# pic32.net
KiCad netlist of a schematic drawn in EAGLE
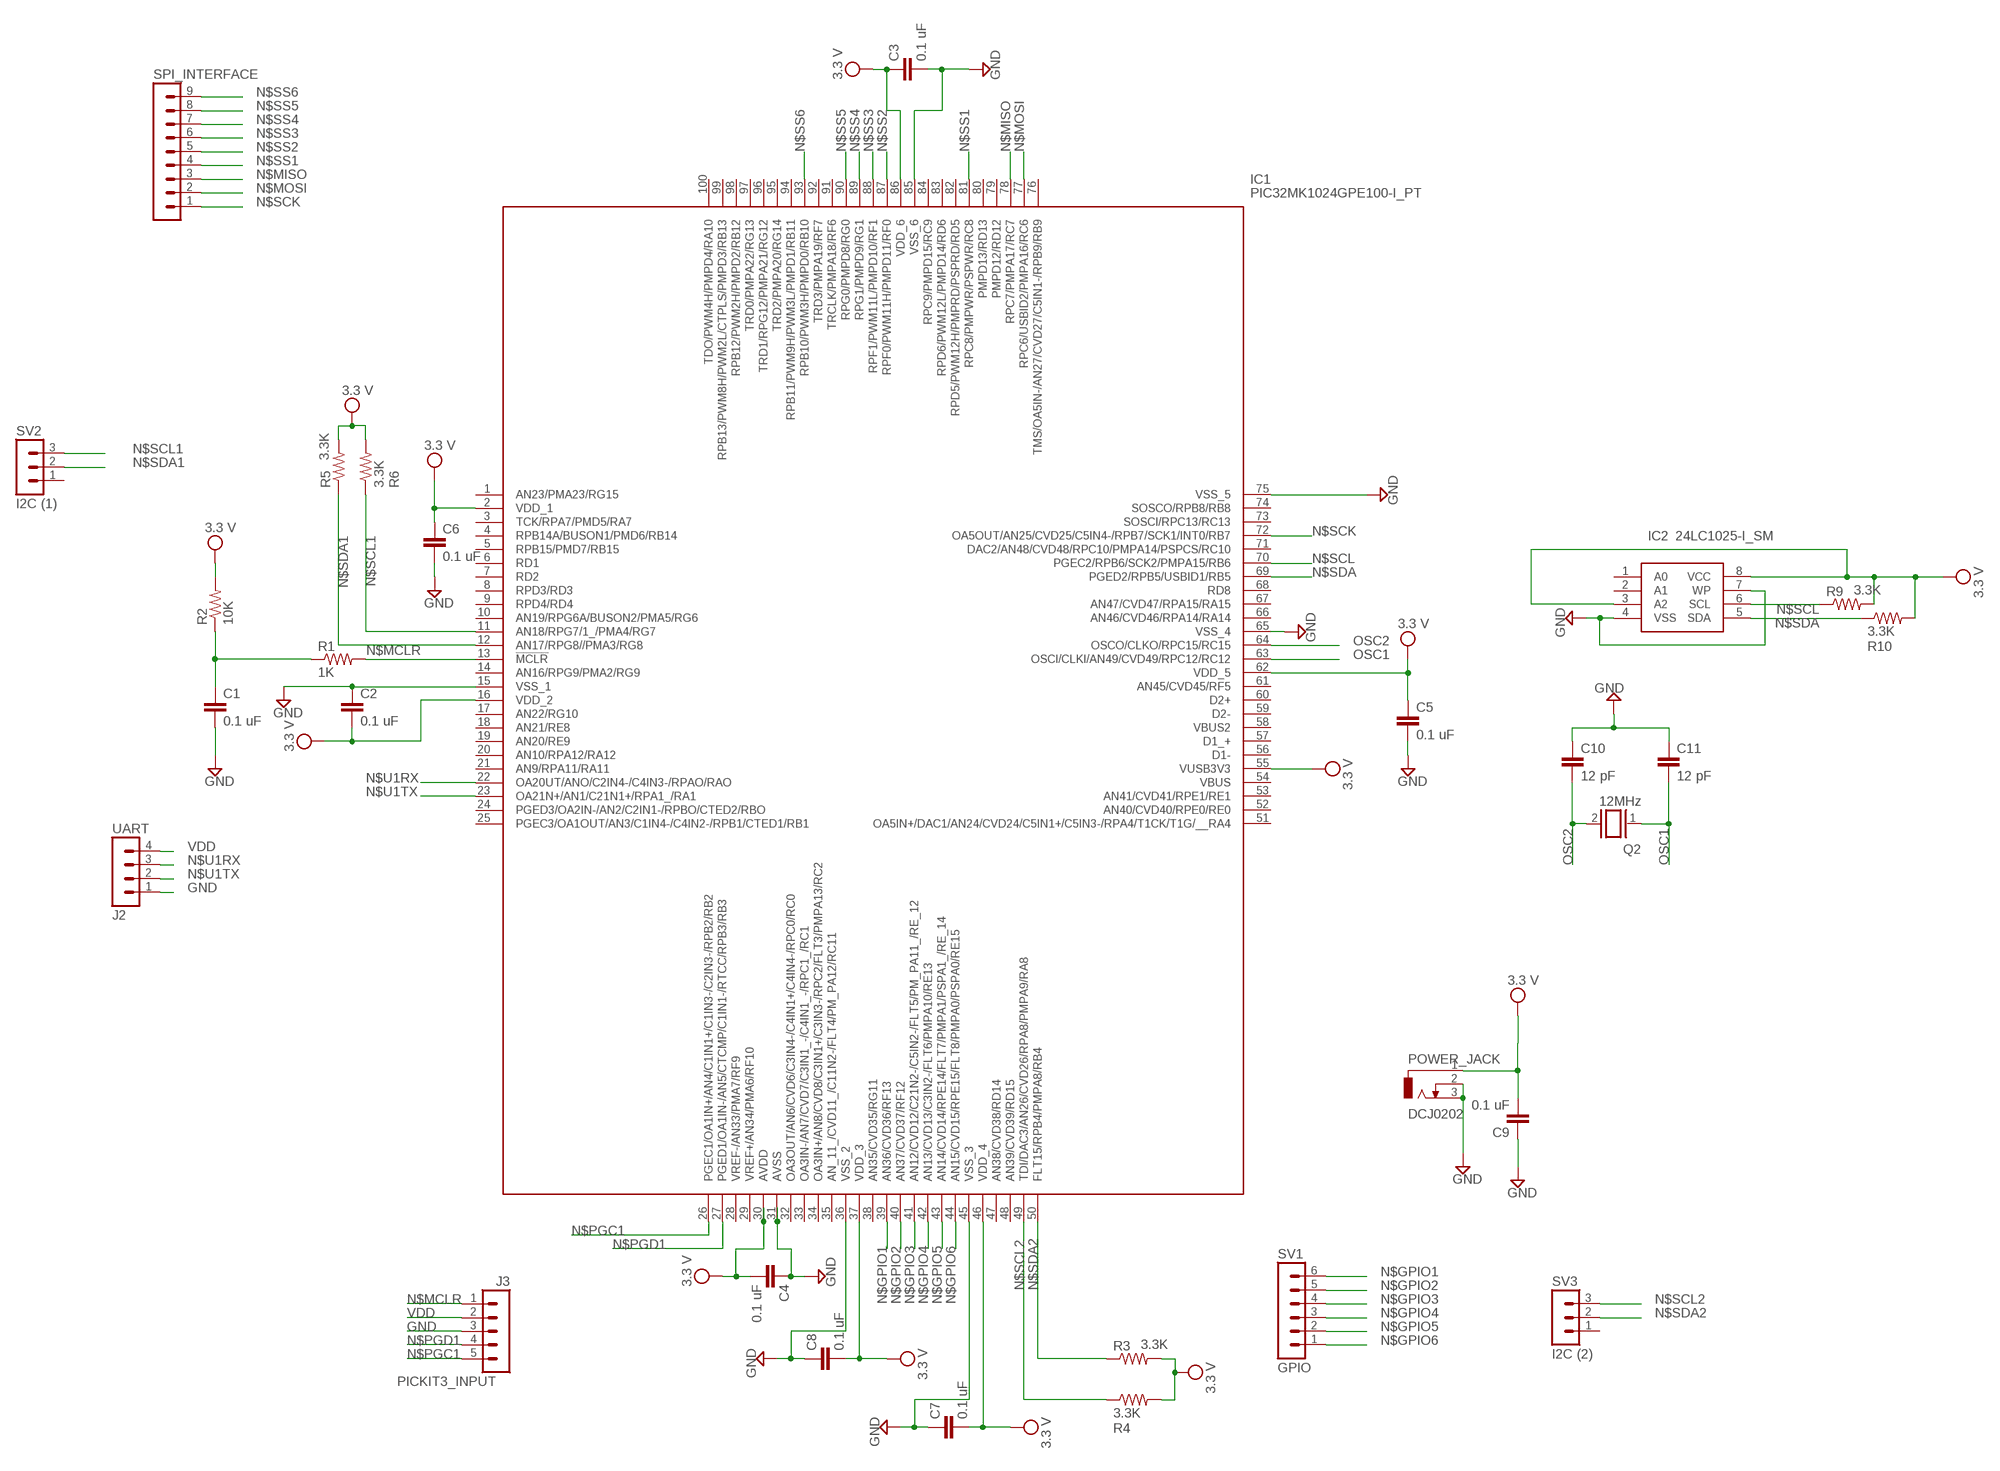
[diagram p0: schematic, sheet 1]

(export (version "E")
  (design (tool "Eeschema 10.0.6"))
  (components
    (comp (ref "C1")
      (value "0.1 uF")
      (footprint "eagle-import:C025-025X050")
      (libsource (lib "eagle-import") (part "C-EU025-025X050"))
    )
    (comp (ref "C2")
      (value "0.1 uF")
      (footprint "eagle-import:C025-025X050")
      (libsource (lib "eagle-import") (part "C-EU025-025X050"))
    )
    (comp (ref "C3")
      (value "0.1 uF")
      (footprint "eagle-import:C025-025X050")
      (libsource (lib "eagle-import") (part "C-EU025-025X050"))
    )
    (comp (ref "C4")
      (value "0.1 uF")
      (footprint "eagle-import:C025-025X050")
      (libsource (lib "eagle-import") (part "C-EU025-025X050"))
    )
    (comp (ref "C5")
      (value "0.1 uF")
      (footprint "eagle-import:C025-025X050")
      (libsource (lib "eagle-import") (part "C-EU025-025X050"))
    )
    (comp (ref "C6")
      (value "0.1 uF")
      (footprint "eagle-import:C025-025X050")
      (libsource (lib "eagle-import") (part "C-EU025-025X050"))
    )
    (comp (ref "C7")
      (value "0.1 uF")
      (footprint "eagle-import:C025-025X050")
      (libsource (lib "eagle-import") (part "C-EU025-025X050"))
    )
    (comp (ref "C8")
      (value "0.1 uF")
      (footprint "eagle-import:C025-025X050")
      (libsource (lib "eagle-import") (part "C-EU025-025X050"))
    )
    (comp (ref "C9")
      (value "0.1 uF")
      (footprint "eagle-import:C025-025X050")
      (libsource (lib "eagle-import") (part "C-EU025-025X050"))
    )
    (comp (ref "C10")
      (value "12 pF")
      (footprint "eagle-import:C025-025X050")
      (libsource (lib "eagle-import") (part "C-EU025-025X050"))
    )
    (comp (ref "C11")
      (value "12 pF")
      (footprint "eagle-import:C025-025X050")
      (libsource (lib "eagle-import") (part "C-EU025-025X050"))
    )
    (comp (ref "IC1")
      (value "PIC32MK1024GPE100-I_PT")
      (footprint "eagle-import:QFP40P1400X1400X120-100N")
      (fields
        (field (name "MANUFACTURER_PART_NUMBER") "PIC32MK1024GPE100-I/PT")
        (field (name "MOUSER_PART_NUMBER") "579-2MK1024GPE100IPT")
      )
      (libsource (lib "eagle-import") (part "PIC32MK1024GPE100-I_PT"))
    )
    (comp (ref "IC2")
      (value "24LC1025-I_SM")
      (footprint "eagle-import:SOIC127P794X203-8N")
      (fields
        (field (name "MANUFACTURER_PART_NUMBER") "24LC1025-I/SM")
        (field (name "MOUSER_PART_NUMBER") "579-24LC1025-I/SM")
      )
      (libsource (lib "eagle-import") (part "24LC1025-I_SM"))
    )
    (comp (ref "PICKIT3_INPUT")
      (value "J3")
      (footprint "eagle-import:MA05-1")
      (libsource (lib "eagle-import") (part "MA05-1"))
    )
    (comp (ref "POWER_JACK")
      (value "DCJ0202")
      (footprint "eagle-import:DCJ0202")
      (libsource (lib "eagle-import") (part "DCJ0202"))
    )
    (comp (ref "Q2")
      (value "12MHz")
      (footprint "eagle-import:QS")
      (libsource (lib "eagle-import") (part "XTAL/S"))
    )
    (comp (ref "R1")
      (value "1K")
      (footprint "eagle-import:0207_7")
      (libsource (lib "eagle-import") (part "R-US_0207/7"))
    )
    (comp (ref "R2")
      (value "10K")
      (footprint "eagle-import:0207_7")
      (libsource (lib "eagle-import") (part "R-US_0207/7"))
    )
    (comp (ref "R3")
      (value "3.3K")
      (footprint "eagle-import:0207_7")
      (libsource (lib "eagle-import") (part "R-US_0207/7"))
    )
    (comp (ref "R4")
      (value "3.3K")
      (footprint "eagle-import:0207_7")
      (libsource (lib "eagle-import") (part "R-US_0207/7"))
    )
    (comp (ref "R5")
      (value "3.3K")
      (footprint "eagle-import:0207_7")
      (libsource (lib "eagle-import") (part "R-US_0207/7"))
    )
    (comp (ref "R6")
      (value "3.3K")
      (footprint "eagle-import:0207_7")
      (libsource (lib "eagle-import") (part "R-US_0207/7"))
    )
    (comp (ref "R9")
      (value "3.3K")
      (footprint "eagle-import:0207_7")
      (libsource (lib "eagle-import") (part "R-US_0207/7"))
    )
    (comp (ref "R10")
      (value "3.3K")
      (footprint "eagle-import:0207_7")
      (libsource (lib "eagle-import") (part "R-US_0207/7"))
    )
    (comp (ref "SPI_INTERFACE")
      (value "J1")
      (footprint "eagle-import:MA09-1")
      (libsource (lib "eagle-import") (part "MA09-1"))
    )
    (comp (ref "SV1")
      (value "GPIO")
      (footprint "eagle-import:MA06-1")
      (libsource (lib "eagle-import") (part "MA06-1"))
    )
    (comp (ref "SV2")
      (value "I2C (1)")
      (footprint "eagle-import:MA03-1")
      (libsource (lib "eagle-import") (part "MA03-1"))
    )
    (comp (ref "SV3")
      (value "I2C (2)")
      (footprint "eagle-import:MA03-1")
      (libsource (lib "eagle-import") (part "MA03-1"))
    )
    (comp (ref "UART")
      (value "J2")
      (footprint "eagle-import:MA04-1")
      (libsource (lib "eagle-import") (part "MA04-1"))
    )
  )
  (nets
    (net (code "1") (name "/N$GPIO1") (class "Default")
      (node (ref "IC1") (pin "39") (pinfunction "AN36/CVD36/RF13_39") (pintype "bidirectional"))
      (node (ref "SV1") (pin "6") (pinfunction "6_6") (pintype "passive"))
    )
    (net (code "2") (name "/N$GPIO2") (class "Default")
      (node (ref "IC1") (pin "40") (pinfunction "AN37/CVD37/RF12_40") (pintype "bidirectional"))
      (node (ref "SV1") (pin "5") (pinfunction "5_5") (pintype "passive"))
    )
    (net (code "3") (name "/N$GPIO3") (class "Default")
      (node (ref "IC1") (pin "41") (pinfunction "AN12/CVD12/C21N2-/C5IN2-/FLT5/PM_PA11_/RE_12_41") (pintype "bidirectional"))
      (node (ref "SV1") (pin "4") (pinfunction "4_4") (pintype "passive"))
    )
    (net (code "4") (name "/N$GPIO4") (class "Default")
      (node (ref "IC1") (pin "42") (pinfunction "AN13/CVD13/C3IN2-/FLT6/PMPA10/RE13_42") (pintype "bidirectional"))
      (node (ref "SV1") (pin "3") (pinfunction "3_3") (pintype "passive"))
    )
    (net (code "5") (name "/N$GPIO5") (class "Default")
      (node (ref "IC1") (pin "43") (pinfunction "AN14/CVD14/RPE14/FLT7/PMPA1/PSPA1_/RE_14_43") (pintype "bidirectional"))
      (node (ref "SV1") (pin "2") (pinfunction "2_2") (pintype "passive"))
    )
    (net (code "6") (name "/N$GPIO6") (class "Default")
      (node (ref "IC1") (pin "44") (pinfunction "AN15/CVD15/RPE15/FLT8/PMPA0/PSPA0/RE15_44") (pintype "bidirectional"))
      (node (ref "SV1") (pin "1") (pinfunction "1_1") (pintype "passive"))
    )
    (net (code "7") (name "/N$MCLR") (class "Default")
      (node (ref "IC1") (pin "13") (pinfunction "~{MCLR}_13") (pintype "bidirectional"))
      (node (ref "PICKIT3_INPUT") (pin "1") (pinfunction "1_1") (pintype "passive"))
      (node (ref "R1") (pin "2") (pinfunction "2_2") (pintype "passive"))
    )
    (net (code "8") (name "/N$MISO") (class "Default")
      (node (ref "IC1") (pin "78") (pinfunction "RPC7/PMPA17/RC7_78") (pintype "bidirectional"))
      (node (ref "SPI_INTERFACE") (pin "3") (pinfunction "3_3") (pintype "passive"))
    )
    (net (code "9") (name "/N$MOSI") (class "Default")
      (node (ref "IC1") (pin "77") (pinfunction "RPC6/USBID2/PMPA16/RC6_77") (pintype "bidirectional"))
      (node (ref "SPI_INTERFACE") (pin "2") (pinfunction "2_2") (pintype "passive"))
    )
    (net (code "10") (name "/N$PGC1") (class "Default")
      (node (ref "IC1") (pin "26") (pinfunction "PGEC1/OA1IN+/AN4/C1IN1+/C1IN3-/C2IN3-/RPB2/RB2_26") (pintype "bidirectional"))
      (node (ref "PICKIT3_INPUT") (pin "5") (pinfunction "5_5") (pintype "passive"))
    )
    (net (code "11") (name "/N$PGD1") (class "Default")
      (node (ref "IC1") (pin "27") (pinfunction "PGED1/OA1IN-/AN5/CTCMP/C1IN1-/RTCC/RPB3/RB3_27") (pintype "bidirectional"))
      (node (ref "PICKIT3_INPUT") (pin "4") (pinfunction "4_4") (pintype "passive"))
    )
    (net (code "12") (name "/N$SCK") (class "Default")
      (node (ref "IC1") (pin "72") (pinfunction "OA5OUT/AN25/CVD25/C5IN4-/RPB7/SCK1/INT0/RB7_72") (pintype "bidirectional"))
      (node (ref "SPI_INTERFACE") (pin "1") (pinfunction "1_1") (pintype "passive"))
    )
    (net (code "13") (name "/N$SCL") (class "Default")
      (node (ref "IC1") (pin "70") (pinfunction "PGEC2/RPB6/SCK2/PMPA15/RB6_70") (pintype "bidirectional"))
      (node (ref "IC2") (pin "6") (pinfunction "SCL_6") (pintype "bidirectional"))
      (node (ref "R9") (pin "1") (pinfunction "1_1") (pintype "passive"))
    )
    (net (code "14") (name "/N$SCL1") (class "Default")
      (node (ref "IC1") (pin "11") (pinfunction "AN18/RPG7/1_/PMA4/RG7_11") (pintype "bidirectional"))
      (node (ref "R6") (pin "1") (pinfunction "1_1") (pintype "passive"))
      (node (ref "SV2") (pin "3") (pinfunction "3_3") (pintype "passive"))
    )
    (net (code "15") (name "/N$SCL2") (class "Default")
      (node (ref "IC1") (pin "49") (pinfunction "TDI/DAC3/AN26/CVD26/RPA8/PMPA9/RA8_49") (pintype "bidirectional"))
      (node (ref "R4") (pin "1") (pinfunction "1_1") (pintype "passive"))
      (node (ref "SV3") (pin "3") (pinfunction "3_3") (pintype "passive"))
    )
    (net (code "16") (name "/N$SDA") (class "Default")
      (node (ref "IC1") (pin "69") (pinfunction "PGED2/RPB5/USBID1/RB5_69") (pintype "bidirectional"))
      (node (ref "IC2") (pin "5") (pinfunction "SDA_5") (pintype "bidirectional"))
      (node (ref "R10") (pin "1") (pinfunction "1_1") (pintype "passive"))
    )
    (net (code "17") (name "/N$SDA1") (class "Default")
      (node (ref "IC1") (pin "12") (pinfunction "AN17/RPG8//PMA3/RG8_12") (pintype "bidirectional"))
      (node (ref "R5") (pin "1") (pinfunction "1_1") (pintype "passive"))
      (node (ref "SV2") (pin "2") (pinfunction "2_2") (pintype "passive"))
    )
    (net (code "18") (name "/N$SDA2") (class "Default")
      (node (ref "IC1") (pin "50") (pinfunction "FLT15/RPB4/PMPA8/RB4_50") (pintype "bidirectional"))
      (node (ref "R3") (pin "1") (pinfunction "1_1") (pintype "passive"))
      (node (ref "SV3") (pin "2") (pinfunction "2_2") (pintype "passive"))
    )
    (net (code "19") (name "/N$SS1") (class "Default")
      (node (ref "IC1") (pin "81") (pinfunction "RPC8/PMPWR/PSPWR/RC8_81") (pintype "bidirectional"))
      (node (ref "SPI_INTERFACE") (pin "4") (pinfunction "4_4") (pintype "passive"))
    )
    (net (code "20") (name "/N$SS2") (class "Default")
      (node (ref "IC1") (pin "87") (pinfunction "RPF0/PWM11H/PMPD11/RF0_87") (pintype "bidirectional"))
      (node (ref "SPI_INTERFACE") (pin "5") (pinfunction "5_5") (pintype "passive"))
    )
    (net (code "21") (name "/N$SS3") (class "Default")
      (node (ref "IC1") (pin "88") (pinfunction "RPF1/PWM11L/PMPD10/RF1_88") (pintype "bidirectional"))
      (node (ref "SPI_INTERFACE") (pin "6") (pinfunction "6_6") (pintype "passive"))
    )
    (net (code "22") (name "/N$SS4") (class "Default")
      (node (ref "IC1") (pin "89") (pinfunction "RPG1/PMPD9/RG1_89") (pintype "bidirectional"))
      (node (ref "SPI_INTERFACE") (pin "7") (pinfunction "7_7") (pintype "passive"))
    )
    (net (code "23") (name "/N$SS5") (class "Default")
      (node (ref "IC1") (pin "90") (pinfunction "RPG0/PMPD8/RG0_90") (pintype "bidirectional"))
      (node (ref "SPI_INTERFACE") (pin "8") (pinfunction "8_8") (pintype "passive"))
    )
    (net (code "24") (name "/N$SS6") (class "Default")
      (node (ref "IC1") (pin "93") (pinfunction "RPB10/PWM3H/PMPD0/RB10_93") (pintype "bidirectional"))
      (node (ref "SPI_INTERFACE") (pin "9") (pinfunction "9_9") (pintype "passive"))
    )
    (net (code "25") (name "/N$U1RX") (class "Default")
      (node (ref "IC1") (pin "22") (pinfunction "OA20UT/ANO/C2IN4-/C4IN3-/RPAO/RAO_22") (pintype "bidirectional"))
      (node (ref "UART") (pin "3") (pinfunction "3_3") (pintype "passive"))
    )
    (net (code "26") (name "/N$U1TX") (class "Default")
      (node (ref "IC1") (pin "23") (pinfunction "OA21N+/AN1/C21N1+/RPA1_/RA1_23") (pintype "bidirectional"))
      (node (ref "UART") (pin "2") (pinfunction "2_2") (pintype "passive"))
    )
    (net (code "27") (name "/OSC1") (class "Default")
      (node (ref "C11") (pin "2") (pinfunction "2_2") (pintype "passive"))
      (node (ref "IC1") (pin "63") (pinfunction "OSCI/CLKI/AN49/CVD49/RPC12/RC12_63") (pintype "bidirectional"))
      (node (ref "Q2") (pin "1") (pinfunction "1_1") (pintype "passive"))
    )
    (net (code "28") (name "/OSC2") (class "Default")
      (node (ref "C10") (pin "2") (pinfunction "2_2") (pintype "passive"))
      (node (ref "IC1") (pin "64") (pinfunction "OSCO/CLKO/RPC15/RC15_64") (pintype "bidirectional"))
      (node (ref "Q2") (pin "2") (pinfunction "2_2") (pintype "passive"))
    )
    (net (code "29") (name "3.3 V") (class "Default")
      (node (ref "C2") (pin "2") (pinfunction "2_2") (pintype "passive"))
      (node (ref "C3") (pin "1") (pinfunction "1_1") (pintype "passive"))
      (node (ref "C4") (pin "2") (pinfunction "2_2") (pintype "passive"))
      (node (ref "C5") (pin "1") (pinfunction "1_1") (pintype "passive"))
      (node (ref "C6") (pin "1") (pinfunction "1_1") (pintype "passive"))
      (node (ref "C7") (pin "2") (pinfunction "2_2") (pintype "passive"))
      (node (ref "C8") (pin "2") (pinfunction "2_2") (pintype "passive"))
      (node (ref "C9") (pin "2") (pinfunction "2_2") (pintype "passive"))
      (node (ref "IC1") (pin "16") (pinfunction "VDD_2_16") (pintype "bidirectional"))
      (node (ref "IC1") (pin "2") (pinfunction "VDD_1_2") (pintype "bidirectional"))
      (node (ref "IC1") (pin "30") (pinfunction "AVDD_30") (pintype "bidirectional"))
      (node (ref "IC1") (pin "37") (pinfunction "VDD_3_37") (pintype "bidirectional"))
      (node (ref "IC1") (pin "46") (pinfunction "VDD_4_46") (pintype "bidirectional"))
      (node (ref "IC1") (pin "55") (pinfunction "VUSB3V3_55") (pintype "bidirectional"))
      (node (ref "IC1") (pin "62") (pinfunction "VDD_5_62") (pintype "bidirectional"))
      (node (ref "IC1") (pin "86") (pinfunction "VDD_6_86") (pintype "bidirectional"))
      (node (ref "IC2") (pin "3") (pinfunction "A2_3") (pintype "bidirectional"))
      (node (ref "IC2") (pin "8") (pinfunction "VCC_8") (pintype "power_in"))
      (node (ref "PICKIT3_INPUT") (pin "2") (pinfunction "2_2") (pintype "passive"))
      (node (ref "POWER_JACK") (pin "1") (pinfunction "1_1") (pintype "passive"))
      (node (ref "R10") (pin "2") (pinfunction "2_2") (pintype "passive"))
      (node (ref "R2") (pin "2") (pinfunction "2_2") (pintype "passive"))
      (node (ref "R3") (pin "2") (pinfunction "2_2") (pintype "passive"))
      (node (ref "R4") (pin "2") (pinfunction "2_2") (pintype "passive"))
      (node (ref "R5") (pin "2") (pinfunction "2_2") (pintype "passive"))
      (node (ref "R6") (pin "2") (pinfunction "2_2") (pintype "passive"))
      (node (ref "R9") (pin "2") (pinfunction "2_2") (pintype "passive"))
      (node (ref "UART") (pin "4") (pinfunction "4_4") (pintype "passive"))
    )
    (net (code "30") (name "GND") (class "Default")
      (node (ref "C1") (pin "2") (pinfunction "2_2") (pintype "passive"))
      (node (ref "C10") (pin "1") (pinfunction "1_1") (pintype "passive"))
      (node (ref "C11") (pin "1") (pinfunction "1_1") (pintype "passive"))
      (node (ref "C2") (pin "1") (pinfunction "1_1") (pintype "passive"))
      (node (ref "C3") (pin "2") (pinfunction "2_2") (pintype "passive"))
      (node (ref "C4") (pin "1") (pinfunction "1_1") (pintype "passive"))
      (node (ref "C5") (pin "2") (pinfunction "2_2") (pintype "passive"))
      (node (ref "C6") (pin "2") (pinfunction "2_2") (pintype "passive"))
      (node (ref "C7") (pin "1") (pinfunction "1_1") (pintype "passive"))
      (node (ref "C8") (pin "1") (pinfunction "1_1") (pintype "passive"))
      (node (ref "C9") (pin "1") (pinfunction "1_1") (pintype "passive"))
      (node (ref "IC1") (pin "15") (pinfunction "VSS_1_15") (pintype "bidirectional"))
      (node (ref "IC1") (pin "31") (pinfunction "AVSS_31") (pintype "bidirectional"))
      (node (ref "IC1") (pin "36") (pinfunction "VSS_2_36") (pintype "bidirectional"))
      (node (ref "IC1") (pin "45") (pinfunction "VSS_3_45") (pintype "bidirectional"))
      (node (ref "IC1") (pin "65") (pinfunction "VSS_4_65") (pintype "bidirectional"))
      (node (ref "IC1") (pin "75") (pinfunction "VSS_5_75") (pintype "bidirectional"))
      (node (ref "IC1") (pin "85") (pinfunction "VSS_6_85") (pintype "bidirectional"))
      (node (ref "IC2") (pin "4") (pinfunction "VSS_4") (pintype "power_in"))
      (node (ref "IC2") (pin "7") (pinfunction "WP_7") (pintype "bidirectional"))
      (node (ref "PICKIT3_INPUT") (pin "3") (pinfunction "3_3") (pintype "passive"))
      (node (ref "POWER_JACK") (pin "2") (pinfunction "2_2") (pintype "passive"))
      (node (ref "POWER_JACK") (pin "3") (pinfunction "3_3") (pintype "passive"))
      (node (ref "UART") (pin "1") (pinfunction "1_1") (pintype "passive"))
    )
    (net (code "31") (name "Net-(C1-Pad1)") (class "Default")
      (node (ref "C1") (pin "1") (pinfunction "1_1") (pintype "passive"))
      (node (ref "R1") (pin "1") (pinfunction "1_1") (pintype "passive"))
      (node (ref "R2") (pin "1") (pinfunction "1_1") (pintype "passive"))
    )
    (net (code "32") (name "unconnected-(IC1-AN9{slash}RPA11{slash}RA11-Pad21)") (class "Default")
      (node (ref "IC1") (pin "21") (pinfunction "AN9/RPA11/RA11_21") (pintype "bidirectional"))
    )
    (net (code "33") (name "unconnected-(IC1-AN10{slash}RPA12{slash}RA12-Pad20)") (class "Default")
      (node (ref "IC1") (pin "20") (pinfunction "AN10/RPA12/RA12_20") (pintype "bidirectional"))
    )
    (net (code "34") (name "unconnected-(IC1-AN16{slash}RPG9{slash}PMA2{slash}RG9-Pad14)") (class "Default")
      (node (ref "IC1") (pin "14") (pinfunction "AN16/RPG9/PMA2/RG9_14") (pintype "bidirectional"))
    )
    (net (code "35") (name "unconnected-(IC1-AN19{slash}RPG6A{slash}BUSON2{slash}PMA5{slash}RG6-Pad10)") (class "Default")
      (node (ref "IC1") (pin "10") (pinfunction "AN19/RPG6A/BUSON2/PMA5/RG6_10") (pintype "bidirectional"))
    )
    (net (code "36") (name "unconnected-(IC1-AN20{slash}RE9-Pad19)") (class "Default")
      (node (ref "IC1") (pin "19") (pinfunction "AN20/RE9_19") (pintype "bidirectional"))
    )
    (net (code "37") (name "unconnected-(IC1-AN21{slash}RE8-Pad18)") (class "Default")
      (node (ref "IC1") (pin "18") (pinfunction "AN21/RE8_18") (pintype "bidirectional"))
    )
    (net (code "38") (name "unconnected-(IC1-AN22{slash}RG10-Pad17)") (class "Default")
      (node (ref "IC1") (pin "17") (pinfunction "AN22/RG10_17") (pintype "bidirectional"))
    )
    (net (code "39") (name "unconnected-(IC1-AN23{slash}PMA23{slash}RG15-Pad1)") (class "Default")
      (node (ref "IC1") (pin "1") (pinfunction "AN23/PMA23/RG15_1") (pintype "bidirectional"))
    )
    (net (code "40") (name "unconnected-(IC1-AN35{slash}CVD35{slash}RG11-Pad38)") (class "Default")
      (node (ref "IC1") (pin "38") (pinfunction "AN35/CVD35/RG11_38") (pintype "bidirectional"))
    )
    (net (code "41") (name "unconnected-(IC1-AN38{slash}CVD38{slash}RD14-Pad47)") (class "Default")
      (node (ref "IC1") (pin "47") (pinfunction "AN38/CVD38/RD14_47") (pintype "bidirectional"))
    )
    (net (code "42") (name "unconnected-(IC1-AN39{slash}CVD39{slash}RD15-Pad48)") (class "Default")
      (node (ref "IC1") (pin "48") (pinfunction "AN39/CVD39/RD15_48") (pintype "bidirectional"))
    )
    (net (code "43") (name "unconnected-(IC1-AN40{slash}CVD40{slash}RPE0{slash}RE0-Pad52)") (class "Default")
      (node (ref "IC1") (pin "52") (pinfunction "AN40/CVD40/RPE0/RE0_52") (pintype "bidirectional"))
    )
    (net (code "44") (name "unconnected-(IC1-AN41{slash}CVD41{slash}RPE1{slash}RE1-Pad53)") (class "Default")
      (node (ref "IC1") (pin "53") (pinfunction "AN41/CVD41/RPE1/RE1_53") (pintype "bidirectional"))
    )
    (net (code "45") (name "unconnected-(IC1-AN45{slash}CVD45{slash}RF5-Pad61)") (class "Default")
      (node (ref "IC1") (pin "61") (pinfunction "AN45/CVD45/RF5_61") (pintype "bidirectional"))
    )
    (net (code "46") (name "unconnected-(IC1-AN46{slash}CVD46{slash}RPA14{slash}RA14-Pad66)") (class "Default")
      (node (ref "IC1") (pin "66") (pinfunction "AN46/CVD46/RPA14/RA14_66") (pintype "bidirectional"))
    )
    (net (code "47") (name "unconnected-(IC1-AN47{slash}CVD47{slash}RPA15{slash}RA15-Pad67)") (class "Default")
      (node (ref "IC1") (pin "67") (pinfunction "AN47/CVD47/RPA15/RA15_67") (pintype "bidirectional"))
    )
    (net (code "48") (name "unconnected-(IC1-AN_11_{slash}CVD11_{slash}C11N2-{slash}FLT4{slash}PM_PA12{slash}RC11-Pad35)") (class "Default")
      (node (ref "IC1") (pin "35") (pinfunction "AN_11_/CVD11_/C11N2-/FLT4/PM_PA12/RC11_35") (pintype "bidirectional"))
    )
    (net (code "49") (name "unconnected-(IC1-D1--Pad56)") (class "Default")
      (node (ref "IC1") (pin "56") (pinfunction "D1-_56") (pintype "bidirectional"))
    )
    (net (code "50") (name "unconnected-(IC1-D1_+-Pad57)") (class "Default")
      (node (ref "IC1") (pin "57") (pinfunction "D1_+_57") (pintype "bidirectional"))
    )
    (net (code "51") (name "unconnected-(IC1-D2+-Pad60)") (class "Default")
      (node (ref "IC1") (pin "60") (pinfunction "D2+_60") (pintype "bidirectional"))
    )
    (net (code "52") (name "unconnected-(IC1-D2--Pad59)") (class "Default")
      (node (ref "IC1") (pin "59") (pinfunction "D2-_59") (pintype "bidirectional"))
    )
    (net (code "53") (name "unconnected-(IC1-DAC2{slash}AN48{slash}CVD48{slash}RPC10{slash}PMPA14{slash}PSPCS{slash}RC10-Pad71)") (class "Default")
      (node (ref "IC1") (pin "71") (pinfunction "DAC2/AN48/CVD48/RPC10/PMPA14/PSPCS/RC10_71") (pintype "bidirectional"))
    )
    (net (code "54") (name "unconnected-(IC1-OA3IN+{slash}AN8{slash}CVD8{slash}C3IN1+{slash}C3IN3-{slash}RPC2{slash}FLT3{slash}PMPA13{slash}RC2-Pad34)") (class "Default")
      (node (ref "IC1") (pin "34") (pinfunction "OA3IN+/AN8/CVD8/C3IN1+/C3IN3-/RPC2/FLT3/PMPA13/RC2_34") (pintype "bidirectional"))
    )
    (net (code "55") (name "unconnected-(IC1-OA3IN-{slash}AN7{slash}CVD7{slash}C3IN1_-{slash}C4IN1_-{slash}RPC1_{slash}RC1-Pad33)") (class "Default")
      (node (ref "IC1") (pin "33") (pinfunction "OA3IN-/AN7/CVD7/C3IN1_-/C4IN1_-/RPC1_/RC1_33") (pintype "bidirectional"))
    )
    (net (code "56") (name "unconnected-(IC1-OA3OUT{slash}AN6{slash}CVD6{slash}C3IN4-{slash}C4IN1+{slash}C4IN4-{slash}RPC0{slash}RC0-Pad32)") (class "Default")
      (node (ref "IC1") (pin "32") (pinfunction "OA3OUT/AN6/CVD6/C3IN4-/C4IN1+/C4IN4-/RPC0/RC0_32") (pintype "bidirectional"))
    )
    (net (code "57") (name "unconnected-(IC1-OA5IN+{slash}DAC1{slash}AN24{slash}CVD24{slash}C5IN1+{slash}C5IN3-{slash}RPA4{slash}T1CK{slash}T1G{slash}__RA4-Pad51)") (class "Default")
      (node (ref "IC1") (pin "51") (pinfunction "OA5IN+/DAC1/AN24/CVD24/C5IN1+/C5IN3-/RPA4/T1CK/T1G/__RA4_51") (pintype "bidirectional"))
    )
    (net (code "58") (name "unconnected-(IC1-PGEC3{slash}OA1OUT{slash}AN3{slash}C1IN4-{slash}C4IN2-{slash}RPB1{slash}CTED1{slash}RB1-Pad25)") (class "Default")
      (node (ref "IC1") (pin "25") (pinfunction "PGEC3/OA1OUT/AN3/C1IN4-/C4IN2-/RPB1/CTED1/RB1_25") (pintype "bidirectional"))
    )
    (net (code "59") (name "unconnected-(IC1-PGED3{slash}OA2IN-{slash}AN2{slash}C2IN1-{slash}RPBO{slash}CTED2{slash}RBO-Pad24)") (class "Default")
      (node (ref "IC1") (pin "24") (pinfunction "PGED3/OA2IN-/AN2/C2IN1-/RPBO/CTED2/RBO_24") (pintype "bidirectional"))
    )
    (net (code "60") (name "unconnected-(IC1-PMPD12{slash}RD12-Pad79)") (class "Default")
      (node (ref "IC1") (pin "79") (pinfunction "PMPD12/RD12_79") (pintype "bidirectional"))
    )
    (net (code "61") (name "unconnected-(IC1-PMPD13{slash}RD13-Pad80)") (class "Default")
      (node (ref "IC1") (pin "80") (pinfunction "PMPD13/RD13_80") (pintype "bidirectional"))
    )
    (net (code "62") (name "unconnected-(IC1-RD1-Pad6)") (class "Default")
      (node (ref "IC1") (pin "6") (pinfunction "RD1_6") (pintype "bidirectional"))
    )
    (net (code "63") (name "unconnected-(IC1-RD2-Pad7)") (class "Default")
      (node (ref "IC1") (pin "7") (pinfunction "RD2_7") (pintype "bidirectional"))
    )
    (net (code "64") (name "unconnected-(IC1-RD8-Pad68)") (class "Default")
      (node (ref "IC1") (pin "68") (pinfunction "RD8_68") (pintype "bidirectional"))
    )
    (net (code "65") (name "unconnected-(IC1-RPB11{slash}PWM9H{slash}PWM3L{slash}PMPD1{slash}RB11-Pad94)") (class "Default")
      (node (ref "IC1") (pin "94") (pinfunction "RPB11/PWM9H/PWM3L/PMPD1/RB11_94") (pintype "bidirectional"))
    )
    (net (code "66") (name "unconnected-(IC1-RPB12{slash}PWM2H{slash}PMPD2{slash}RB12-Pad98)") (class "Default")
      (node (ref "IC1") (pin "98") (pinfunction "RPB12/PWM2H/PMPD2/RB12_98") (pintype "bidirectional"))
    )
    (net (code "67") (name "unconnected-(IC1-RPB13{slash}PWM8H{slash}PWM2L{slash}CTPLS{slash}PMPD3{slash}RB13-Pad99)") (class "Default")
      (node (ref "IC1") (pin "99") (pinfunction "RPB13/PWM8H/PWM2L/CTPLS/PMPD3/RB13_99") (pintype "bidirectional"))
    )
    (net (code "68") (name "unconnected-(IC1-RPB14A{slash}BUSON1{slash}PMD6{slash}RB14-Pad4)") (class "Default")
      (node (ref "IC1") (pin "4") (pinfunction "RPB14A/BUSON1/PMD6/RB14_4") (pintype "bidirectional"))
    )
    (net (code "69") (name "unconnected-(IC1-RPB15{slash}PMD7{slash}RB15-Pad5)") (class "Default")
      (node (ref "IC1") (pin "5") (pinfunction "RPB15/PMD7/RB15_5") (pintype "bidirectional"))
    )
    (net (code "70") (name "unconnected-(IC1-RPC9{slash}PMPD15{slash}RC9-Pad84)") (class "Default")
      (node (ref "IC1") (pin "84") (pinfunction "RPC9/PMPD15/RC9_84") (pintype "bidirectional"))
    )
    (net (code "71") (name "unconnected-(IC1-RPD3{slash}RD3-Pad8)") (class "Default")
      (node (ref "IC1") (pin "8") (pinfunction "RPD3/RD3_8") (pintype "bidirectional"))
    )
    (net (code "72") (name "unconnected-(IC1-RPD4{slash}RD4-Pad9)") (class "Default")
      (node (ref "IC1") (pin "9") (pinfunction "RPD4/RD4_9") (pintype "bidirectional"))
    )
    (net (code "73") (name "unconnected-(IC1-RPD5{slash}PWM12H{slash}PMPRD{slash}PSPRD{slash}RD5-Pad82)") (class "Default")
      (node (ref "IC1") (pin "82") (pinfunction "RPD5/PWM12H/PMPRD/PSPRD/RD5_82") (pintype "bidirectional"))
    )
    (net (code "74") (name "unconnected-(IC1-RPD6{slash}PWM12L{slash}PMPD14{slash}RD6-Pad83)") (class "Default")
      (node (ref "IC1") (pin "83") (pinfunction "RPD6/PWM12L/PMPD14/RD6_83") (pintype "bidirectional"))
    )
    (net (code "75") (name "unconnected-(IC1-SOSCI{slash}RPC13{slash}RC13-Pad73)") (class "Default")
      (node (ref "IC1") (pin "73") (pinfunction "SOSCI/RPC13/RC13_73") (pintype "bidirectional"))
    )
    (net (code "76") (name "unconnected-(IC1-SOSCO{slash}RPB8{slash}RB8-Pad74)") (class "Default")
      (node (ref "IC1") (pin "74") (pinfunction "SOSCO/RPB8/RB8_74") (pintype "bidirectional"))
    )
    (net (code "77") (name "unconnected-(IC1-TCK{slash}RPA7{slash}PMD5{slash}RA7-Pad3)") (class "Default")
      (node (ref "IC1") (pin "3") (pinfunction "TCK/RPA7/PMD5/RA7_3") (pintype "bidirectional"))
    )
    (net (code "78") (name "unconnected-(IC1-TDO{slash}PWM4H{slash}PMPD4{slash}RA10-Pad100)") (class "Default")
      (node (ref "IC1") (pin "100") (pinfunction "TDO/PWM4H/PMPD4/RA10_100") (pintype "bidirectional"))
    )
    (net (code "79") (name "unconnected-(IC1-TMS{slash}OA5IN-{slash}AN27{slash}CVD27{slash}C5IN1-{slash}RPB9{slash}RB9-Pad76)") (class "Default")
      (node (ref "IC1") (pin "76") (pinfunction "TMS/OA5IN-/AN27/CVD27/C5IN1-/RPB9/RB9_76") (pintype "bidirectional"))
    )
    (net (code "80") (name "unconnected-(IC1-TRCLK{slash}PMPA18{slash}RF6-Pad91)") (class "Default")
      (node (ref "IC1") (pin "91") (pinfunction "TRCLK/PMPA18/RF6_91") (pintype "bidirectional"))
    )
    (net (code "81") (name "unconnected-(IC1-TRD0{slash}PMPA22{slash}RG13-Pad97)") (class "Default")
      (node (ref "IC1") (pin "97") (pinfunction "TRD0/PMPA22/RG13_97") (pintype "bidirectional"))
    )
    (net (code "82") (name "unconnected-(IC1-TRD1{slash}RPG12{slash}PMPA21{slash}RG12-Pad96)") (class "Default")
      (node (ref "IC1") (pin "96") (pinfunction "TRD1/RPG12/PMPA21/RG12_96") (pintype "bidirectional"))
    )
    (net (code "83") (name "unconnected-(IC1-TRD2{slash}PMPA20{slash}RG14-Pad95)") (class "Default")
      (node (ref "IC1") (pin "95") (pinfunction "TRD2/PMPA20/RG14_95") (pintype "bidirectional"))
    )
    (net (code "84") (name "unconnected-(IC1-TRD3{slash}PMPA19{slash}RF7-Pad92)") (class "Default")
      (node (ref "IC1") (pin "92") (pinfunction "TRD3/PMPA19/RF7_92") (pintype "bidirectional"))
    )
    (net (code "85") (name "unconnected-(IC1-VBUS-Pad54)") (class "Default")
      (node (ref "IC1") (pin "54") (pinfunction "VBUS_54") (pintype "bidirectional"))
    )
    (net (code "86") (name "unconnected-(IC1-VBUS2-Pad58)") (class "Default")
      (node (ref "IC1") (pin "58") (pinfunction "VBUS2_58") (pintype "bidirectional"))
    )
    (net (code "87") (name "unconnected-(IC1-VREF+{slash}AN34{slash}PMA6{slash}RF10-Pad29)") (class "Default")
      (node (ref "IC1") (pin "29") (pinfunction "VREF+/AN34/PMA6/RF10_29") (pintype "bidirectional"))
    )
    (net (code "88") (name "unconnected-(IC1-VREF-{slash}AN33{slash}PMA7{slash}RF9-Pad28)") (class "Default")
      (node (ref "IC1") (pin "28") (pinfunction "VREF-/AN33/PMA7/RF9_28") (pintype "bidirectional"))
    )
    (net (code "89") (name "unconnected-(IC2-A0-Pad1)") (class "Default")
      (node (ref "IC2") (pin "1") (pinfunction "A0_1") (pintype "bidirectional"))
    )
    (net (code "90") (name "unconnected-(IC2-A1-Pad2)") (class "Default")
      (node (ref "IC2") (pin "2") (pinfunction "A1_2") (pintype "bidirectional"))
    )
    (net (code "91") (name "unconnected-(SV2-Pad1)") (class "Default")
      (node (ref "SV2") (pin "1") (pinfunction "1_1") (pintype "passive"))
    )
    (net (code "92") (name "unconnected-(SV3-Pad1)") (class "Default")
      (node (ref "SV3") (pin "1") (pinfunction "1_1") (pintype "passive"))
    )
  )
)
